# ST-link_V2.net
KiCad netlist of a schematic drawn in Altium Designer
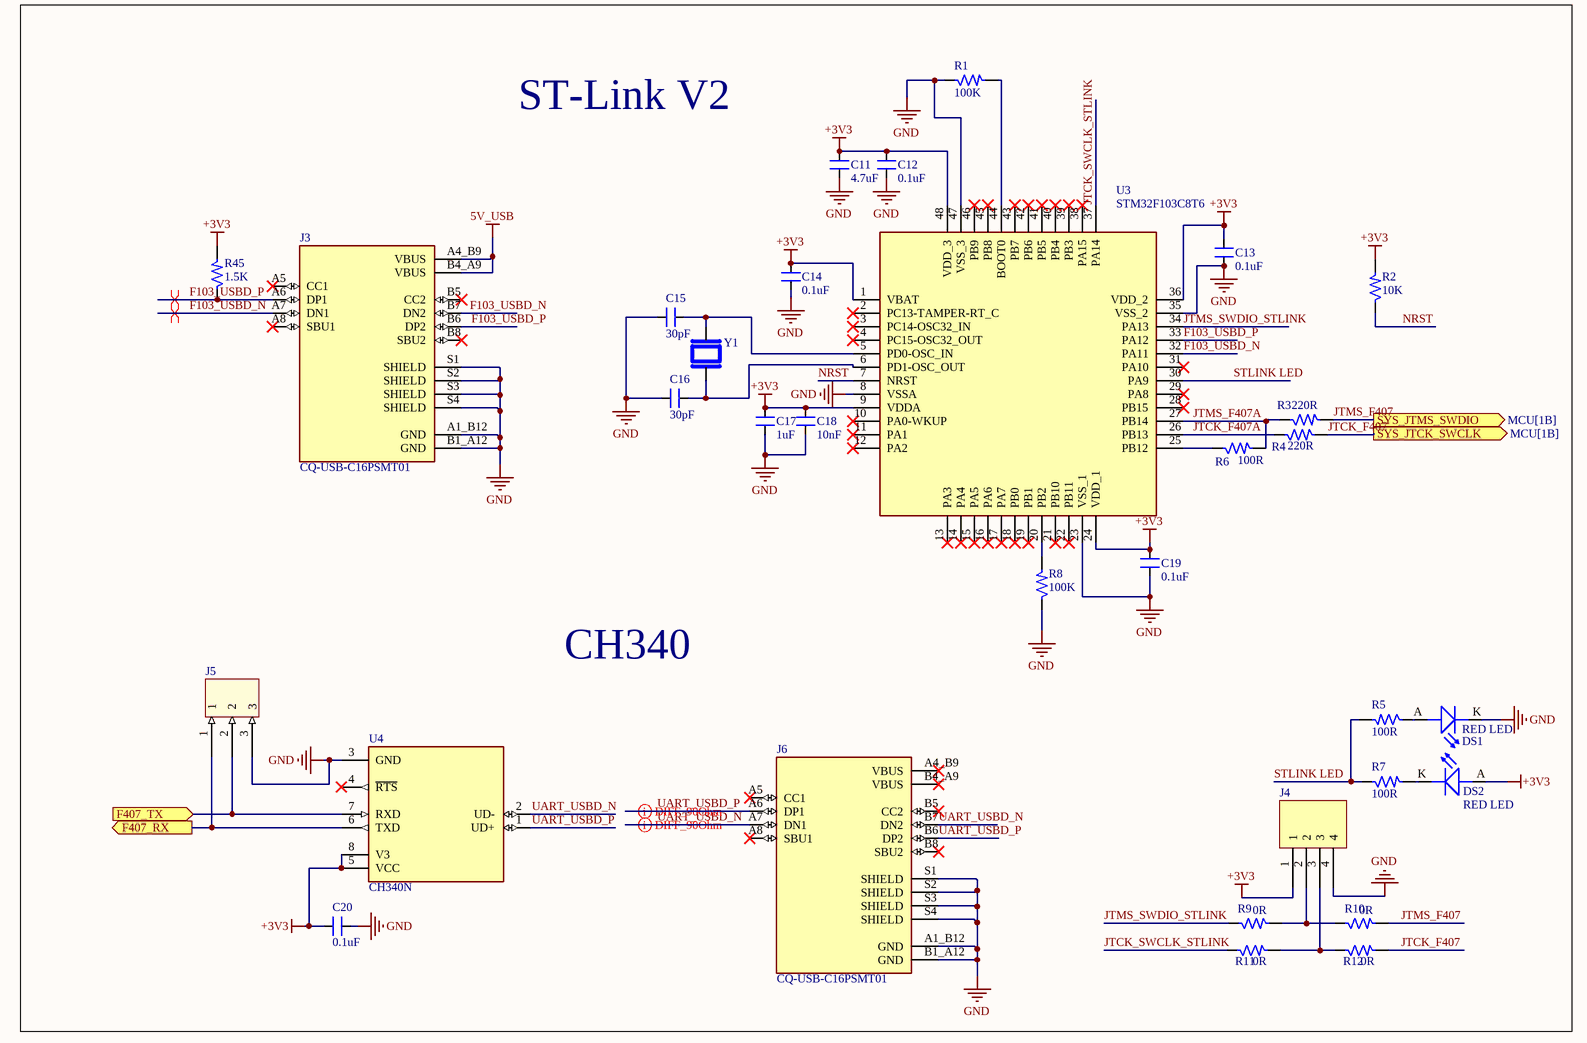
[diagram p0: ST-link V2.SchDoc]

(export (version "E")
  (design (tool "Eeschema 10.0.6"))
  (components
    (comp (ref "C11")
      (value "4.7uF")
      (footprint "CAP_0805")
      (description "4.7µF ±10% 50V Ceramic Capacitor X5R 0805 (2012 Metric)")
      (fields
        (field (name "MANUFACTURER") "Yageo")
        (field (name "MANUFACTURER PART NUMBER") "GRM21BR61H475KE51L")
      )
      (libsource (lib "ESTEEMPCBLIB") (part "CAP_4.7uF-50V-10%-0805"))
    )
    (comp (ref "C12")
      (value "0.1uF")
      (footprint "CAP_0805")
      (description "0.1µF ±10% 50V Ceramic Capacitor X7R 0805 (2012 Metric)")
      (fields
        (field (name "MANUFACTURER") "Samsung")
        (field (name "MANUFACTURER PART NUMBER") "CL21B104KBCNNNC")
      )
      (libsource (lib "ESTEEMPCBLIB") (part "CAP_0.1uF-50V-10%-0805"))
    )
    (comp (ref "C13")
      (value "0.1uF")
      (footprint "CAP_0805")
      (description "0.1µF ±10% 50V Ceramic Capacitor X7R 0805 (2012 Metric)")
      (fields
        (field (name "MANUFACTURER") "Samsung")
        (field (name "MANUFACTURER PART NUMBER") "CL21B104KBCNNNC")
      )
      (libsource (lib "ESTEEMPCBLIB") (part "CAP_0.1uF-50V-10%-0805"))
    )
    (comp (ref "C14")
      (value "0.1uF")
      (footprint "CAP_0805")
      (description "0.1µF ±10% 50V Ceramic Capacitor X7R 0805 (2012 Metric)")
      (fields
        (field (name "MANUFACTURER") "Samsung")
        (field (name "MANUFACTURER PART NUMBER") "CL21B104KBCNNNC")
      )
      (libsource (lib "ESTEEMPCBLIB") (part "CAP_0.1uF-50V-10%-0805"))
    )
    (comp (ref "C15")
      (value "30pF")
      (footprint "CAP_0805")
      (description "±10% 50V Ceramic Capacitor C0G, NP0 0805 (2012 Metric)")
      (fields
        (field (name "MANUFACTURER PART NUMBER") "C0805C300K5GAC7800")
        (field (name "MANUFACTURER") "KEMET")
      )
      (libsource (lib "ESTEEMPCBLIB") (part "CAP_30pF-50V-10%-0805"))
    )
    (comp (ref "C16")
      (value "30pF")
      (footprint "CAP_0805")
      (description "±10% 50V Ceramic Capacitor C0G, NP0 0805 (2012 Metric)")
      (fields
        (field (name "MANUFACTURER PART NUMBER") "C0805C300K5GAC7800")
        (field (name "MANUFACTURER") "KEMET")
      )
      (libsource (lib "ESTEEMPCBLIB") (part "CAP_30pF-50V-10%-0805"))
    )
    (comp (ref "C17")
      (value "1uF")
      (footprint "CAP_0805")
      (description "1µF ±5% 50V Ceramic Capacitor X7R 0805 (2012 Metric)")
      (fields
        (field (name "MANUFACTURER") "Samsung")
        (field (name "MANUFACTURER PART NUMBER") "CC0805JKX7R9BB105")
      )
      (libsource (lib "ESTEEMPCBLIB") (part "CAP_1uF-50V-5%-0805"))
    )
    (comp (ref "C18")
      (value "10nF")
      (footprint "CAP_0805")
      (description "10000pF ±10% 50V Ceramic Capacitor X7R 0805 (2012 Metric)")
      (fields
        (field (name "MANUFACTURER") "Samsung")
        (field (name "MANUFACTURER PART NUMBER") "C0805C103K5RECAUTO")
      )
      (libsource (lib "ESTEEMPCBLIB") (part "CAP_10nF-50V-10%-0805"))
    )
    (comp (ref "C19")
      (value "0.1uF")
      (footprint "CAP_0805")
      (description "0.1µF ±10% 50V Ceramic Capacitor X7R 0805 (2012 Metric)")
      (fields
        (field (name "MANUFACTURER") "Samsung")
        (field (name "MANUFACTURER PART NUMBER") "CL21B104KBCNNNC")
      )
      (libsource (lib "ESTEEMPCBLIB") (part "CAP_0.1uF-50V-10%-0805"))
    )
    (comp (ref "C20")
      (value "0.1uF")
      (footprint "CAP_0805")
      (description "0.1µF ±10% 50V Ceramic Capacitor X7R 0805 (2012 Metric)")
      (fields
        (field (name "MANUFACTURER") "Samsung")
        (field (name "MANUFACTURER PART NUMBER") "CL21B104KBCNNNC")
      )
      (libsource (lib "ESTEEMPCBLIB") (part "CAP_0.1uF-50V-10%-0805"))
    )
    (comp (ref "DS1")
      (value "RED LED")
      (footprint "LED_0805")
      (description "Red 631nm LED Indication - Discrete 2V 0805 (2012 Metric)")
      (fields
        (field (name "MANUFACTURER") "Vishay Lite-On")
        (field (name "MANUFACTURER PART NUMBER") "LTST-C171KRKT")
      )
      (libsource (lib "ESTEEMPCBLIB") (part "LED_RED-2V-20mA-0805"))
    )
    (comp (ref "DS2")
      (value "RED LED")
      (footprint "LED_0805")
      (description "Red 631nm LED Indication - Discrete 2V 0805 (2012 Metric)")
      (fields
        (field (name "MANUFACTURER") "Vishay Lite-On")
        (field (name "MANUFACTURER PART NUMBER") "LTST-C171KRKT")
      )
      (libsource (lib "ESTEEMPCBLIB") (part "LED_RED-2V-20mA-0805"))
    )
    (comp (ref "J3")
      (value "CQ-USB-C16PSMT01")
      (footprint "SHENZHEN-CHUANGQIN-TECHNOLOGY_CQ-USB-C16PSMT01")
      (description "C Type USB Type-C Female Plug 16 Pin Connector Power Charger Jack Port")
      (fields (field (name "MF") "Shenzen Chuangqin Technology"))
      (libsource (lib "Persional LIB") (part "CQ-USB-C16PSMT01"))
    )
    (comp (ref "J4")
      (value "4X1 BERG STRIP")
      (footprint "CON4_100_40D72_TH_ST_MALE")
      (description "4 Pins, 1 Row 2.54mm Pitch, Straight bergstrip, Male")
      (fields (field (name "MANUFACTURER") "NA"))
      (libsource (lib "ESTEEMPCBLIB") (part "CON-BS-PLG_4X1-100-ST-TH"))
    )
    (comp (ref "J5")
      (value "3X1 BERG STRIP")
      (footprint "CON3_100_40D72_TH_ST-MALE")
      (description "3 Pins, 1 Row 2.54mm Pitch, Straight bergstrip, Male")
      (fields (field (name "MANUFACTURER PART NUMBER") "RKI-1140") (field (name "MANUFACTURER") "NA"))
      (libsource (lib "ESTEEMPCBLIB") (part "CON-BS-PLG_3X1-100-ST-TH"))
    )
    (comp (ref "J6")
      (value "CQ-USB-C16PSMT01")
      (footprint "SHENZHEN-CHUANGQIN-TECHNOLOGY_CQ-USB-C16PSMT01")
      (description "C Type USB Type-C Female Plug 16 Pin Connector Power Charger Jack Port")
      (fields (field (name "MF") "Shenzen Chuangqin Technology"))
      (libsource (lib "Persional LIB") (part "CQ-USB-C16PSMT01"))
    )
    (comp (ref "R1")
      (value "100K")
      (footprint "RES_0603")
      (description "100 kOhms ±1% 0.1W, 1/10W Chip Resistor 0603 (1608 Metric) Automotive AEC-Q200 Thick Film")
      (fields
        (field (name "MANUFACTURER") "Stackpole Electronics")
        (field (name "MANUFACTURER PART NUMBER") "RMCF0603FT100K")
      )
      (libsource (lib "ESTEEMPCBLIB") (part "RES_100K-0.1W-1%-0603"))
    )
    (comp (ref "R2")
      (value "10K")
      (footprint "RES_0603")
      (description "10 kOhms ±1% 0.1W, 1/10W Chip Resistor 0603 (1608 Metric) Automotive AEC-Q200 Thick Film")
      (fields (field (name "MANUFACTURER") "Walsin") (field (name "MANUFACTURER PART NUMBER") "WR06X1002FTL"))
      (libsource (lib "ESTEEMPCBLIB") (part "RES_10K-0.1W-1%-0603"))
    )
    (comp (ref "R3")
      (value "220R")
      (footprint "RES_0805")
      (description "220 Ohms ±1% 0.125W, 1/8W Chip Resistor 0805 (2012 Metric) Automotive AEC-Q200 Thick Film")
      (fields (field (name "MANUFACTURER") "Walsin") (field (name "MANUFACTURER PART NUMBER") "WR08X2200FTL"))
      (libsource (lib "ESTEEMPCBLIB") (part "RES_220R-0.125W-1%-0805"))
    )
    (comp (ref "R4")
      (value "220R")
      (footprint "RES_0805")
      (description "220 Ohms ±1% 0.125W, 1/8W Chip Resistor 0805 (2012 Metric) Automotive AEC-Q200 Thick Film")
      (fields (field (name "MANUFACTURER") "Walsin") (field (name "MANUFACTURER PART NUMBER") "WR08X2200FTL"))
      (libsource (lib "ESTEEMPCBLIB") (part "RES_220R-0.125W-1%-0805"))
    )
    (comp (ref "R5")
      (value "100R")
      (footprint "RES_0805")
      (fields (field (name "MANUFACTURER") "Walsin") (field (name "MANUFACTURER PART NUMBER") "WR08X1000FTL"))
      (libsource (lib "ESTEEMPCBLIB") (part "RES_100R-0.125W-1%-0805"))
    )
    (comp (ref "R6")
      (value "100R")
      (footprint "RES_0805")
      (fields (field (name "MANUFACTURER") "Walsin") (field (name "MANUFACTURER PART NUMBER") "WR08X1000FTL"))
      (libsource (lib "ESTEEMPCBLIB") (part "RES_100R-0.125W-1%-0805"))
    )
    (comp (ref "R7")
      (value "100R")
      (footprint "RES_0805")
      (fields (field (name "MANUFACTURER") "Walsin") (field (name "MANUFACTURER PART NUMBER") "WR08X1000FTL"))
      (libsource (lib "ESTEEMPCBLIB") (part "RES_100R-0.125W-1%-0805"))
    )
    (comp (ref "R8")
      (value "100K")
      (footprint "RES_0603")
      (description "100 kOhms ±1% 0.1W, 1/10W Chip Resistor 0603 (1608 Metric) Automotive AEC-Q200 Thick Film")
      (fields
        (field (name "MANUFACTURER") "Stackpole Electronics")
        (field (name "MANUFACTURER PART NUMBER") "RMCF0603FT100K")
      )
      (libsource (lib "ESTEEMPCBLIB") (part "RES_100K-0.1W-1%-0603"))
    )
    (comp (ref "R9")
      (value "0R")
      (footprint "RES_0805")
      (description "0 Ohms Jumper 0.125W, 1/8W Chip Resistor 0805 (2012 Metric) Automotive AEC-Q200 Thick Film")
      (fields (field (name "MANUFACTURER") "Walsin") (field (name "MANUFACTURER PART NUMBER") "WR08X000PTL"))
      (libsource (lib "ESTEEMPCBLIB") (part "RES_0R-0.125W-1%-0805"))
    )
    (comp (ref "R10")
      (value "0R")
      (footprint "RES_0805")
      (description "0 Ohms Jumper 0.125W, 1/8W Chip Resistor 0805 (2012 Metric) Automotive AEC-Q200 Thick Film")
      (fields (field (name "MANUFACTURER") "Walsin") (field (name "MANUFACTURER PART NUMBER") "WR08X000PTL"))
      (libsource (lib "ESTEEMPCBLIB") (part "RES_0R-0.125W-1%-0805"))
    )
    (comp (ref "R11")
      (value "0R")
      (footprint "RES_0805")
      (description "0 Ohms Jumper 0.125W, 1/8W Chip Resistor 0805 (2012 Metric) Automotive AEC-Q200 Thick Film")
      (fields (field (name "MANUFACTURER") "Walsin") (field (name "MANUFACTURER PART NUMBER") "WR08X000PTL"))
      (libsource (lib "ESTEEMPCBLIB") (part "RES_0R-0.125W-1%-0805"))
    )
    (comp (ref "R12")
      (value "0R")
      (footprint "RES_0805")
      (description "0 Ohms Jumper 0.125W, 1/8W Chip Resistor 0805 (2012 Metric) Automotive AEC-Q200 Thick Film")
      (fields (field (name "MANUFACTURER") "Walsin") (field (name "MANUFACTURER PART NUMBER") "WR08X000PTL"))
      (libsource (lib "ESTEEMPCBLIB") (part "RES_0R-0.125W-1%-0805"))
    )
    (comp (ref "R45")
      (value "1.5K")
      (footprint "RES_0805")
      (description "1.5 kOhms ±1% 0.125W, 1/8W Chip Resistor 0805 (2012 Metric) Thick Film")
      (fields
        (field (name "MANUFACTURER") "TE Connectivity Passive Product")
        (field (name "MANUFACTURER PART NUMBER") "CRG0805F1K5")
      )
      (libsource (lib "ESTEEMPCBLIB") (part "RES_1.5K-0.125W-1%-0805"))
    )
    (comp (ref "U3")
      (value "STM32F103C8T6")
      (footprint "LQFP-48_19.6_393_58X11_SMD")
      (description "ARM® Cortex®-M3 STM32F1 Microcontroller IC 32-Bit 72MHz 64KB (64K x 8) FLASH 48-LQFP (7x7)")
      (fields (field (name "MANUFACTURER") "STMicroelectronics"))
      (libsource (lib "ESTEEMPCBLIB") (part "IC_STM32F103C8T6"))
    )
    (comp (ref "U4")
      (value "CH340N")
      (footprint "SOIC127P600X160-8N")
      (description "USB to Serial Port Chip")
      (fields (field (name "MF") "WCH"))
      (libsource (lib "Persional LIB") (part "CH340N"))
    )
    (comp (ref "Y1")
      (value "ATS08A-E")
      (footprint "XTAL_HC49P488W43L1085T450H368")
      (description "8 MHz Â±30ppm Crystal 20pF 60 Ohms HC-49/US")
      (fields (field (name "MF") "CTS"))
      (libsource (lib "Persional LIB") (part "ATS08A-E"))
    )
  )
  (nets
    (net (code "1") (name "+3V3") (class "Default")
      (node (ref "C11") (pin "2") (pinfunction "2_2") (pintype "passive"))
      (node (ref "C12") (pin "2") (pinfunction "2_2") (pintype "passive"))
      (node (ref "C13") (pin "2") (pinfunction "2_2") (pintype "passive"))
      (node (ref "C14") (pin "2") (pinfunction "2_2") (pintype "passive"))
      (node (ref "C17") (pin "2") (pinfunction "2_2") (pintype "passive"))
      (node (ref "C18") (pin "2") (pinfunction "2_2") (pintype "passive"))
      (node (ref "C19") (pin "2") (pinfunction "2_2") (pintype "passive"))
      (node (ref "C20") (pin "2") (pinfunction "2_2") (pintype "passive"))
      (node (ref "DS2") (pin "A") (pinfunction "ANODE_A") (pintype "passive"))
      (node (ref "J4") (pin "1") (pinfunction "1_1") (pintype "passive"))
      (node (ref "R2") (pin "2") (pinfunction "2_2") (pintype "passive"))
      (node (ref "R45") (pin "2") (pinfunction "2_2") (pintype "passive"))
      (node (ref "U3") (pin "1") (pinfunction "VBAT_1") (pintype "passive"))
      (node (ref "U3") (pin "24") (pinfunction "VDD_1_24") (pintype "passive"))
      (node (ref "U3") (pin "36") (pinfunction "VDD_2_36") (pintype "passive"))
      (node (ref "U3") (pin "48") (pinfunction "VDD_3_48") (pintype "passive"))
      (node (ref "U3") (pin "9") (pinfunction "VDDA_9") (pintype "passive"))
      (node (ref "U4") (pin "5") (pinfunction "VCC_5") (pintype "power_in"))
      (node (ref "U4") (pin "8") (pinfunction "V3_8") (pintype "power_in"))
    )
    (net (code "2") (name "/F103_USBD_N") (class "Default")
      (node (ref "J3") (pin "A7") (pinfunction "DN1_A7") (pintype "bidirectional"))
      (node (ref "J3") (pin "B7") (pinfunction "DN2_B7") (pintype "bidirectional"))
      (node (ref "U3") (pin "32") (pinfunction "PA11_32") (pintype "passive"))
    )
    (net (code "3") (name "/F103_USBD_P") (class "Default")
      (node (ref "J3") (pin "A6") (pinfunction "DP1_A6") (pintype "bidirectional"))
      (node (ref "J3") (pin "B6") (pinfunction "DP2_B6") (pintype "bidirectional"))
      (node (ref "R45") (pin "1") (pinfunction "1_1") (pintype "passive"))
      (node (ref "U3") (pin "33") (pinfunction "PA12_33") (pintype "passive"))
    )
    (net (code "4") (name "/F407_RX") (class "Default")
      (node (ref "J5") (pin "1") (pinfunction "1_1") (pintype "input"))
      (node (ref "U4") (pin "6") (pinfunction "TXD_6") (pintype "output"))
    )
    (net (code "5") (name "/F407_TX") (class "Default")
      (node (ref "J5") (pin "2") (pinfunction "2_2") (pintype "input"))
      (node (ref "U4") (pin "7") (pinfunction "RXD_7") (pintype "input"))
    )
    (net (code "6") (name "/JTCK_F407") (class "Default")
      (node (ref "R12") (pin "2") (pinfunction "2_2") (pintype "passive"))
      (node (ref "R4") (pin "2") (pinfunction "2_2") (pintype "passive"))
    )
    (net (code "7") (name "/JTCK_F407A") (class "Default")
      (node (ref "R4") (pin "1") (pinfunction "1_1") (pintype "passive"))
      (node (ref "U3") (pin "26") (pinfunction "PB13_26") (pintype "passive"))
    )
    (net (code "8") (name "/JTCK_SWCLK_STLINK") (class "Default")
      (node (ref "R11") (pin "1") (pinfunction "1_1") (pintype "passive"))
      (node (ref "U3") (pin "37") (pinfunction "PA14_37") (pintype "passive"))
    )
    (net (code "9") (name "/JTMS_F407") (class "Default")
      (node (ref "R10") (pin "2") (pinfunction "2_2") (pintype "passive"))
      (node (ref "R3") (pin "2") (pinfunction "2_2") (pintype "passive"))
    )
    (net (code "10") (name "/JTMS_F407A") (class "Default")
      (node (ref "R3") (pin "1") (pinfunction "1_1") (pintype "passive"))
      (node (ref "R6") (pin "2") (pinfunction "2_2") (pintype "passive"))
      (node (ref "U3") (pin "27") (pinfunction "PB14_27") (pintype "passive"))
    )
    (net (code "11") (name "/JTMS_SWDIO_STLINK") (class "Default")
      (node (ref "R9") (pin "1") (pinfunction "1_1") (pintype "passive"))
      (node (ref "U3") (pin "34") (pinfunction "PA13_34") (pintype "passive"))
    )
    (net (code "12") (name "/NRST") (class "Default")
      (node (ref "R2") (pin "1") (pinfunction "1_1") (pintype "passive"))
      (node (ref "U3") (pin "7") (pinfunction "NRST_7") (pintype "passive"))
    )
    (net (code "13") (name "/STLINK LED") (class "Default")
      (node (ref "R5") (pin "2") (pinfunction "2_2") (pintype "passive"))
      (node (ref "R7") (pin "1") (pinfunction "1_1") (pintype "passive"))
      (node (ref "U3") (pin "30") (pinfunction "PA9_30") (pintype "passive"))
    )
    (net (code "14") (name "/UART_USBD_N") (class "Default")
      (node (ref "J6") (pin "A7") (pinfunction "DN1_A7") (pintype "bidirectional"))
      (node (ref "J6") (pin "B7") (pinfunction "DN2_B7") (pintype "bidirectional"))
      (node (ref "U4") (pin "2") (pinfunction "UD-_2") (pintype "bidirectional"))
    )
    (net (code "15") (name "/UART_USBD_P") (class "Default")
      (node (ref "J6") (pin "A6") (pinfunction "DP1_A6") (pintype "bidirectional"))
      (node (ref "J6") (pin "B6") (pinfunction "DP2_B6") (pintype "bidirectional"))
      (node (ref "U4") (pin "1") (pinfunction "UD+_1") (pintype "bidirectional"))
    )
    (net (code "16") (name "5V_USB") (class "Default")
      (node (ref "J3") (pin "A4_B9") (pinfunction "VBUS_A4_B9") (pintype "power_in"))
      (node (ref "J3") (pin "B4_A9") (pinfunction "VBUS_B4_A9") (pintype "power_in"))
    )
    (net (code "17") (name "GND") (class "Default")
      (node (ref "C11") (pin "1") (pinfunction "1_1") (pintype "passive"))
      (node (ref "C12") (pin "1") (pinfunction "1_1") (pintype "passive"))
      (node (ref "C13") (pin "1") (pinfunction "1_1") (pintype "passive"))
      (node (ref "C14") (pin "1") (pinfunction "1_1") (pintype "passive"))
      (node (ref "C15") (pin "1") (pinfunction "1_1") (pintype "passive"))
      (node (ref "C16") (pin "1") (pinfunction "1_1") (pintype "passive"))
      (node (ref "C17") (pin "1") (pinfunction "1_1") (pintype "passive"))
      (node (ref "C18") (pin "1") (pinfunction "1_1") (pintype "passive"))
      (node (ref "C19") (pin "1") (pinfunction "1_1") (pintype "passive"))
      (node (ref "C20") (pin "1") (pinfunction "1_1") (pintype "passive"))
      (node (ref "DS1") (pin "K") (pinfunction "CATHODE_K") (pintype "passive"))
      (node (ref "J3") (pin "A1_B12") (pinfunction "GND_A1_B12") (pintype "passive"))
      (node (ref "J3") (pin "B1_A12") (pinfunction "GND_B1_A12") (pintype "passive"))
      (node (ref "J3") (pin "S1") (pinfunction "SHIELD_S1") (pintype "passive"))
      (node (ref "J3") (pin "S2") (pinfunction "SHIELD_S2") (pintype "passive"))
      (node (ref "J3") (pin "S3") (pinfunction "SHIELD_S3") (pintype "passive"))
      (node (ref "J3") (pin "S4") (pinfunction "SHIELD_S4") (pintype "passive"))
      (node (ref "J4") (pin "4") (pinfunction "4_4") (pintype "passive"))
      (node (ref "J5") (pin "3") (pinfunction "3_3") (pintype "input"))
      (node (ref "J6") (pin "A1_B12") (pinfunction "GND_A1_B12") (pintype "passive"))
      (node (ref "J6") (pin "B1_A12") (pinfunction "GND_B1_A12") (pintype "passive"))
      (node (ref "J6") (pin "S1") (pinfunction "SHIELD_S1") (pintype "passive"))
      (node (ref "J6") (pin "S2") (pinfunction "SHIELD_S2") (pintype "passive"))
      (node (ref "J6") (pin "S3") (pinfunction "SHIELD_S3") (pintype "passive"))
      (node (ref "J6") (pin "S4") (pinfunction "SHIELD_S4") (pintype "passive"))
      (node (ref "R1") (pin "1") (pinfunction "1_1") (pintype "passive"))
      (node (ref "R8") (pin "1") (pinfunction "1_1") (pintype "passive"))
      (node (ref "U3") (pin "23") (pinfunction "VSS_1_23") (pintype "passive"))
      (node (ref "U3") (pin "35") (pinfunction "VSS_2_35") (pintype "passive"))
      (node (ref "U3") (pin "47") (pinfunction "VSS_3_47") (pintype "passive"))
      (node (ref "U3") (pin "8") (pinfunction "VSSA_8") (pintype "passive"))
      (node (ref "U4") (pin "3") (pinfunction "GND_3") (pintype "passive"))
    )
    (net (code "18") (name "Net-(DS1-ANODE)") (class "Default")
      (node (ref "DS1") (pin "A") (pinfunction "ANODE_A") (pintype "passive"))
      (node (ref "R5") (pin "1") (pinfunction "1_1") (pintype "passive"))
    )
    (net (code "19") (name "Net-(DS2-CATHODE)") (class "Default")
      (node (ref "DS2") (pin "K") (pinfunction "CATHODE_K") (pintype "passive"))
      (node (ref "R7") (pin "2") (pinfunction "2_2") (pintype "passive"))
    )
    (net (code "20") (name "Net-(J4-Pad2)") (class "Default")
      (node (ref "J4") (pin "2") (pinfunction "2_2") (pintype "passive"))
      (node (ref "R10") (pin "1") (pinfunction "1_1") (pintype "passive"))
      (node (ref "R9") (pin "2") (pinfunction "2_2") (pintype "passive"))
    )
    (net (code "21") (name "Net-(J4-Pad3)") (class "Default")
      (node (ref "J4") (pin "3") (pinfunction "3_3") (pintype "passive"))
      (node (ref "R11") (pin "2") (pinfunction "2_2") (pintype "passive"))
      (node (ref "R12") (pin "1") (pinfunction "1_1") (pintype "passive"))
    )
    (net (code "22") (name "Net-(U3-BOOT0)") (class "Default")
      (node (ref "R1") (pin "2") (pinfunction "2_2") (pintype "passive"))
      (node (ref "U3") (pin "44") (pinfunction "BOOT0_44") (pintype "passive"))
    )
    (net (code "23") (name "Net-(U3-PB2)") (class "Default")
      (node (ref "R8") (pin "2") (pinfunction "2_2") (pintype "passive"))
      (node (ref "U3") (pin "20") (pinfunction "PB2_20") (pintype "passive"))
    )
    (net (code "24") (name "Net-(U3-PB12)") (class "Default")
      (node (ref "R6") (pin "1") (pinfunction "1_1") (pintype "passive"))
      (node (ref "U3") (pin "25") (pinfunction "PB12_25") (pintype "passive"))
    )
    (net (code "25") (name "Net-(U3-PD0-OSC_IN)") (class "Default")
      (node (ref "C15") (pin "2") (pinfunction "2_2") (pintype "passive"))
      (node (ref "U3") (pin "5") (pinfunction "PD0-OSC_IN_5") (pintype "passive"))
      (node (ref "Y1") (pin "2") (pinfunction "2_2") (pintype "passive"))
    )
    (net (code "26") (name "Net-(U3-PD1-OSC_OUT)") (class "Default")
      (node (ref "C16") (pin "2") (pinfunction "2_2") (pintype "passive"))
      (node (ref "U3") (pin "6") (pinfunction "PD1-OSC_OUT_6") (pintype "passive"))
      (node (ref "Y1") (pin "1") (pinfunction "1_1") (pintype "passive"))
    )
    (net (code "27") (name "unconnected-(J3-CC1-PadA5)") (class "Default")
      (node (ref "J3") (pin "A5") (pinfunction "CC1_A5") (pintype "bidirectional+no_connect"))
    )
    (net (code "28") (name "unconnected-(J3-CC2-PadB5)") (class "Default")
      (node (ref "J3") (pin "B5") (pinfunction "CC2_B5") (pintype "bidirectional+no_connect"))
    )
    (net (code "29") (name "unconnected-(J3-SBU1-PadA8)") (class "Default")
      (node (ref "J3") (pin "A8") (pinfunction "SBU1_A8") (pintype "bidirectional+no_connect"))
    )
    (net (code "30") (name "unconnected-(J3-SBU2-PadB8)") (class "Default")
      (node (ref "J3") (pin "B8") (pinfunction "SBU2_B8") (pintype "bidirectional+no_connect"))
    )
    (net (code "31") (name "unconnected-(J6-CC1-PadA5)") (class "Default")
      (node (ref "J6") (pin "A5") (pinfunction "CC1_A5") (pintype "bidirectional+no_connect"))
    )
    (net (code "32") (name "unconnected-(J6-CC2-PadB5)") (class "Default")
      (node (ref "J6") (pin "B5") (pinfunction "CC2_B5") (pintype "bidirectional+no_connect"))
    )
    (net (code "33") (name "unconnected-(J6-SBU1-PadA8)") (class "Default")
      (node (ref "J6") (pin "A8") (pinfunction "SBU1_A8") (pintype "bidirectional+no_connect"))
    )
    (net (code "34") (name "unconnected-(J6-SBU2-PadB8)") (class "Default")
      (node (ref "J6") (pin "B8") (pinfunction "SBU2_B8") (pintype "bidirectional+no_connect"))
    )
    (net (code "35") (name "unconnected-(J6-VBUS-PadA4_B9)") (class "Default")
      (node (ref "J6") (pin "A4_B9") (pinfunction "VBUS_A4_B9") (pintype "power_in+no_connect"))
    )
    (net (code "36") (name "unconnected-(J6-VBUS-PadB4_A9)") (class "Default")
      (node (ref "J6") (pin "B4_A9") (pinfunction "VBUS_B4_A9") (pintype "power_in+no_connect"))
    )
    (net (code "37") (name "unconnected-(U3-PA0-WKUP-Pad10)") (class "Default")
      (node (ref "U3") (pin "10") (pinfunction "PA0-WKUP_10") (pintype "passive+no_connect"))
    )
    (net (code "38") (name "unconnected-(U3-PA1-Pad11)") (class "Default")
      (node (ref "U3") (pin "11") (pinfunction "PA1_11") (pintype "passive+no_connect"))
    )
    (net (code "39") (name "unconnected-(U3-PA2-Pad12)") (class "Default")
      (node (ref "U3") (pin "12") (pinfunction "PA2_12") (pintype "passive+no_connect"))
    )
    (net (code "40") (name "unconnected-(U3-PA3-Pad13)") (class "Default")
      (node (ref "U3") (pin "13") (pinfunction "PA3_13") (pintype "passive+no_connect"))
    )
    (net (code "41") (name "unconnected-(U3-PA4-Pad14)") (class "Default")
      (node (ref "U3") (pin "14") (pinfunction "PA4_14") (pintype "passive+no_connect"))
    )
    (net (code "42") (name "unconnected-(U3-PA5-Pad15)") (class "Default")
      (node (ref "U3") (pin "15") (pinfunction "PA5_15") (pintype "passive+no_connect"))
    )
    (net (code "43") (name "unconnected-(U3-PA6-Pad16)") (class "Default")
      (node (ref "U3") (pin "16") (pinfunction "PA6_16") (pintype "passive+no_connect"))
    )
    (net (code "44") (name "unconnected-(U3-PA7-Pad17)") (class "Default")
      (node (ref "U3") (pin "17") (pinfunction "PA7_17") (pintype "passive+no_connect"))
    )
    (net (code "45") (name "unconnected-(U3-PA8-Pad29)") (class "Default")
      (node (ref "U3") (pin "29") (pinfunction "PA8_29") (pintype "passive+no_connect"))
    )
    (net (code "46") (name "unconnected-(U3-PA10-Pad31)") (class "Default")
      (node (ref "U3") (pin "31") (pinfunction "PA10_31") (pintype "passive+no_connect"))
    )
    (net (code "47") (name "unconnected-(U3-PA15-Pad38)") (class "Default")
      (node (ref "U3") (pin "38") (pinfunction "PA15_38") (pintype "passive+no_connect"))
    )
    (net (code "48") (name "unconnected-(U3-PB0-Pad18)") (class "Default")
      (node (ref "U3") (pin "18") (pinfunction "PB0_18") (pintype "passive+no_connect"))
    )
    (net (code "49") (name "unconnected-(U3-PB1-Pad19)") (class "Default")
      (node (ref "U3") (pin "19") (pinfunction "PB1_19") (pintype "passive+no_connect"))
    )
    (net (code "50") (name "unconnected-(U3-PB3-Pad39)") (class "Default")
      (node (ref "U3") (pin "39") (pinfunction "PB3_39") (pintype "passive+no_connect"))
    )
    (net (code "51") (name "unconnected-(U3-PB4-Pad40)") (class "Default")
      (node (ref "U3") (pin "40") (pinfunction "PB4_40") (pintype "passive+no_connect"))
    )
    (net (code "52") (name "unconnected-(U3-PB5-Pad41)") (class "Default")
      (node (ref "U3") (pin "41") (pinfunction "PB5_41") (pintype "passive+no_connect"))
    )
    (net (code "53") (name "unconnected-(U3-PB6-Pad42)") (class "Default")
      (node (ref "U3") (pin "42") (pinfunction "PB6_42") (pintype "passive+no_connect"))
    )
    (net (code "54") (name "unconnected-(U3-PB7-Pad43)") (class "Default")
      (node (ref "U3") (pin "43") (pinfunction "PB7_43") (pintype "passive+no_connect"))
    )
    (net (code "55") (name "unconnected-(U3-PB8-Pad45)") (class "Default")
      (node (ref "U3") (pin "45") (pinfunction "PB8_45") (pintype "passive+no_connect"))
    )
    (net (code "56") (name "unconnected-(U3-PB9-Pad46)") (class "Default")
      (node (ref "U3") (pin "46") (pinfunction "PB9_46") (pintype "passive+no_connect"))
    )
    (net (code "57") (name "unconnected-(U3-PB10-Pad21)") (class "Default")
      (node (ref "U3") (pin "21") (pinfunction "PB10_21") (pintype "passive+no_connect"))
    )
    (net (code "58") (name "unconnected-(U3-PB11-Pad22)") (class "Default")
      (node (ref "U3") (pin "22") (pinfunction "PB11_22") (pintype "passive+no_connect"))
    )
    (net (code "59") (name "unconnected-(U3-PB15-Pad28)") (class "Default")
      (node (ref "U3") (pin "28") (pinfunction "PB15_28") (pintype "passive+no_connect"))
    )
    (net (code "60") (name "unconnected-(U3-PC13-TAMPER-RT_C-Pad2)") (class "Default")
      (node (ref "U3") (pin "2") (pinfunction "PC13-TAMPER-RT_C_2") (pintype "passive+no_connect"))
    )
    (net (code "61") (name "unconnected-(U3-PC14-OSC32_IN-Pad3)") (class "Default")
      (node (ref "U3") (pin "3") (pinfunction "PC14-OSC32_IN_3") (pintype "passive+no_connect"))
    )
    (net (code "62") (name "unconnected-(U3-PC15-OSC32_OUT-Pad4)") (class "Default")
      (node (ref "U3") (pin "4") (pinfunction "PC15-OSC32_OUT_4") (pintype "passive+no_connect"))
    )
    (net (code "63") (name "unconnected-(U4-~{RTS}-Pad4)") (class "Default")
      (node (ref "U4") (pin "4") (pinfunction "~{RTS}_4") (pintype "output+no_connect"))
    )
  )
)
